# H-Bridge_2.net
KiCad netlist of a schematic drawn in Altium Designer
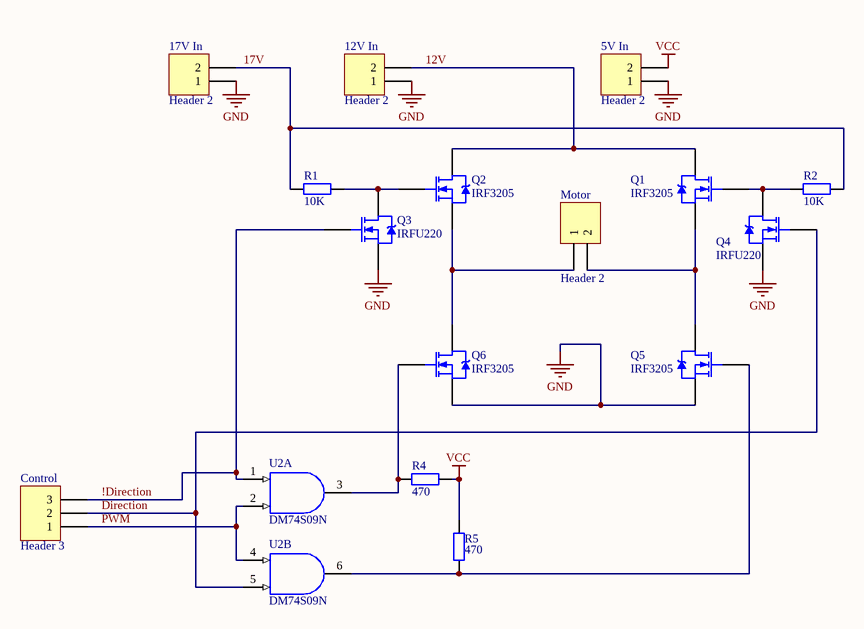
[diagram p0: H-Bridge 2.SchDoc]

(export (version "E")
  (design (tool "Eeschema 10.0.6"))
  (components
    (comp (ref "5V In")
      (value "Header 2")
      (footprint "HDR1X2")
      (description "Header, 2-Pin")
      (fields (field (name "PUBLISHER") "Altium Limited"))
      (libsource (lib "Miscellaneous Connectors") (part "Header 2"))
    )
    (comp (ref "12V In")
      (value "Header 2")
      (footprint "HDR1X2")
      (description "Header, 2-Pin")
      (fields (field (name "PUBLISHER") "Altium Limited"))
      (libsource (lib "Miscellaneous Connectors") (part "Header 2"))
    )
    (comp (ref "17V In")
      (value "Header 2")
      (footprint "HDR1X2")
      (description "Header, 2-Pin")
      (fields (field (name "PUBLISHER") "Altium Limited"))
      (libsource (lib "Miscellaneous Connectors") (part "Header 2"))
    )
    (comp (ref "Control")
      (value "Header 3")
      (footprint "HDR1X3")
      (description "Header, 3-Pin")
      (fields (field (name "PUBLISHER") "Altium Limited"))
      (libsource (lib "Miscellaneous Connectors") (part "Header 3"))
    )
    (comp (ref "Motor")
      (value "Header 2")
      (footprint "HDR1X2")
      (description "Header, 2-Pin")
      (fields (field (name "PUBLISHER") "Altium Limited"))
      (libsource (lib "") (part "Header 2_1"))
    )
    (comp (ref "Q1")
      (value "IRF3205")
      (footprint "TO-220AB")
      (description "HEXFET Power MOSFET")
      (fields (field (name "PUBLISHER") "Altium Limited"))
      (libsource (lib "IR Discrete MOSFET - Power") (part "IRF3205"))
    )
    (comp (ref "Q2")
      (value "IRF3205")
      (footprint "TO-220AB")
      (description "HEXFET Power MOSFET")
      (fields (field (name "PUBLISHER") "Altium Limited"))
      (libsource (lib "IR Discrete MOSFET - Power") (part "IRF3205"))
    )
    (comp (ref "Q3")
      (value "IRFU220")
      (footprint "TO-251AA")
      (description "HEXFET Power MOSFET")
      (fields (field (name "PUBLISHER") "Altium Limited"))
      (libsource (lib "IR Discrete MOSFET - Power") (part "IRFU220"))
    )
    (comp (ref "Q4")
      (value "IRFU220")
      (footprint "TO-251AA")
      (description "HEXFET Power MOSFET")
      (fields (field (name "PUBLISHER") "Altium Limited"))
      (libsource (lib "IR Discrete MOSFET - Power") (part "IRFU220"))
    )
    (comp (ref "Q5")
      (value "IRF3205")
      (footprint "TO-220AB")
      (description "HEXFET Power MOSFET")
      (fields (field (name "PUBLISHER") "Altium Limited"))
      (libsource (lib "IR Discrete MOSFET - Power") (part "IRF3205"))
    )
    (comp (ref "Q6")
      (value "IRF3205")
      (footprint "TO-220AB")
      (description "HEXFET Power MOSFET")
      (fields (field (name "PUBLISHER") "Altium Limited"))
      (libsource (lib "IR Discrete MOSFET - Power") (part "IRF3205"))
    )
    (comp (ref "R1")
      (value "10K")
      (footprint "AXIAL-0.4")
      (description "Resistor")
      (fields (field (name "Comment") "Res2") (field (name "PUBLISHER") "Altium Limited"))
      (libsource (lib "") (part "Res2_3"))
    )
    (comp (ref "R2")
      (value "10K")
      (footprint "AXIAL-0.4")
      (description "Resistor")
      (fields (field (name "Comment") "Res2") (field (name "PUBLISHER") "Altium Limited"))
      (libsource (lib "Miscellaneous Devices") (part "Res2"))
    )
    (comp (ref "R4")
      (value "470")
      (footprint "AXIAL-0.4")
      (description "Resistor")
      (fields (field (name "Comment") "Res2") (field (name "PUBLISHER") "Altium Limited"))
      (libsource (lib "") (part "Res2_2"))
    )
    (comp (ref "R5")
      (value "470")
      (footprint "AXIAL-0.4")
      (description "Resistor")
      (fields (field (name "Comment") "Res2") (field (name "PUBLISHER") "Altium Limited"))
      (libsource (lib "") (part "Res2_1"))
    )
    (comp (ref "U2")
      (value "DM74S09N")
      (footprint "N14A")
      (description "Quad 2-Input AND Gate with Open-Collector Output, 14-Pin PDIP")
      (fields (field (name "PUBLISHER") "Altium Limited"))
      (libsource (lib "FSC Logic Gate") (part "DM74S09N"))
    )
  )
  (nets
    (net (code "1") (name "/!Direction") (class "Default")
      (node (ref "Control") (pin "3") (pinfunction "3_3") (pintype "passive"))
      (node (ref "Q3") (pin "1") (pinfunction "G_1") (pintype "passive"))
      (node (ref "U2") (pin "1") (pinfunction "A_1") (pintype "input"))
    )
    (net (code "2") (name "/12V") (class "Default")
      (node (ref "12V In") (pin "2") (pinfunction "2_2") (pintype "passive"))
      (node (ref "Q1") (pin "2") (pinfunction "D_2") (pintype "passive"))
      (node (ref "Q2") (pin "2") (pinfunction "D_2") (pintype "passive"))
    )
    (net (code "3") (name "/17V") (class "Default")
      (node (ref "17V In") (pin "2") (pinfunction "2_2") (pintype "passive"))
      (node (ref "R1") (pin "1") (pinfunction "1_1") (pintype "passive"))
      (node (ref "R2") (pin "1") (pinfunction "1_1") (pintype "passive"))
    )
    (net (code "4") (name "/Direction") (class "Default")
      (node (ref "Control") (pin "2") (pinfunction "2_2") (pintype "passive"))
      (node (ref "Q4") (pin "1") (pinfunction "G_1") (pintype "passive"))
      (node (ref "U2") (pin "5") (pinfunction "B_5") (pintype "input"))
    )
    (net (code "5") (name "/PWM") (class "Default")
      (node (ref "Control") (pin "1") (pinfunction "1_1") (pintype "passive"))
      (node (ref "U2") (pin "2") (pinfunction "B_2") (pintype "input"))
      (node (ref "U2") (pin "4") (pinfunction "A_4") (pintype "input"))
    )
    (net (code "6") (name "GND") (class "Default")
      (node (ref "12V In") (pin "1") (pinfunction "1_1") (pintype "passive"))
      (node (ref "17V In") (pin "1") (pinfunction "1_1") (pintype "passive"))
      (node (ref "5V In") (pin "1") (pinfunction "1_1") (pintype "passive"))
      (node (ref "Q3") (pin "3") (pinfunction "S_3") (pintype "passive"))
      (node (ref "Q4") (pin "3") (pinfunction "S_3") (pintype "passive"))
      (node (ref "Q5") (pin "3") (pinfunction "S_3") (pintype "passive"))
      (node (ref "Q6") (pin "3") (pinfunction "S_3") (pintype "passive"))
      (node (ref "U2") (pin "7") (pinfunction "GND_7") (pintype "power_in"))
    )
    (net (code "7") (name "Net-(Q1-G)") (class "Default")
      (node (ref "Q1") (pin "1") (pinfunction "G_1") (pintype "passive"))
      (node (ref "Q4") (pin "2") (pinfunction "D_2") (pintype "passive"))
      (node (ref "R2") (pin "2") (pinfunction "2_2") (pintype "passive"))
    )
    (net (code "8") (name "Net-(Q1-S)") (class "Default")
      (node (ref "Motor") (pin "2") (pinfunction "2_2") (pintype "passive"))
      (node (ref "Q1") (pin "3") (pinfunction "S_3") (pintype "passive"))
      (node (ref "Q5") (pin "2") (pinfunction "D_2") (pintype "passive"))
    )
    (net (code "9") (name "Net-(Q2-G)") (class "Default")
      (node (ref "Q2") (pin "1") (pinfunction "G_1") (pintype "passive"))
      (node (ref "Q3") (pin "2") (pinfunction "D_2") (pintype "passive"))
      (node (ref "R1") (pin "2") (pinfunction "2_2") (pintype "passive"))
    )
    (net (code "10") (name "Net-(Q2-S)") (class "Default")
      (node (ref "Motor") (pin "1") (pinfunction "1_1") (pintype "passive"))
      (node (ref "Q2") (pin "3") (pinfunction "S_3") (pintype "passive"))
      (node (ref "Q6") (pin "2") (pinfunction "D_2") (pintype "passive"))
    )
    (net (code "11") (name "Net-(Q5-G)") (class "Default")
      (node (ref "Q5") (pin "1") (pinfunction "G_1") (pintype "passive"))
      (node (ref "R5") (pin "1") (pinfunction "1_1") (pintype "passive"))
      (node (ref "U2") (pin "6") (pinfunction "Y_6") (pintype "open_collector"))
    )
    (net (code "12") (name "Net-(Q6-G)") (class "Default")
      (node (ref "Q6") (pin "1") (pinfunction "G_1") (pintype "passive"))
      (node (ref "R4") (pin "2") (pinfunction "2_2") (pintype "passive"))
      (node (ref "U2") (pin "3") (pinfunction "Y_3") (pintype "open_collector"))
    )
    (net (code "13") (name "VCC") (class "Default")
      (node (ref "5V In") (pin "2") (pinfunction "2_2") (pintype "passive"))
      (node (ref "R4") (pin "1") (pinfunction "1_1") (pintype "passive"))
      (node (ref "R5") (pin "2") (pinfunction "2_2") (pintype "passive"))
      (node (ref "U2") (pin "14") (pinfunction "VCC_14") (pintype "power_in"))
    )
  )
)
